# SHEET1.net
KiCad netlist of a schematic drawn in Altium Designer
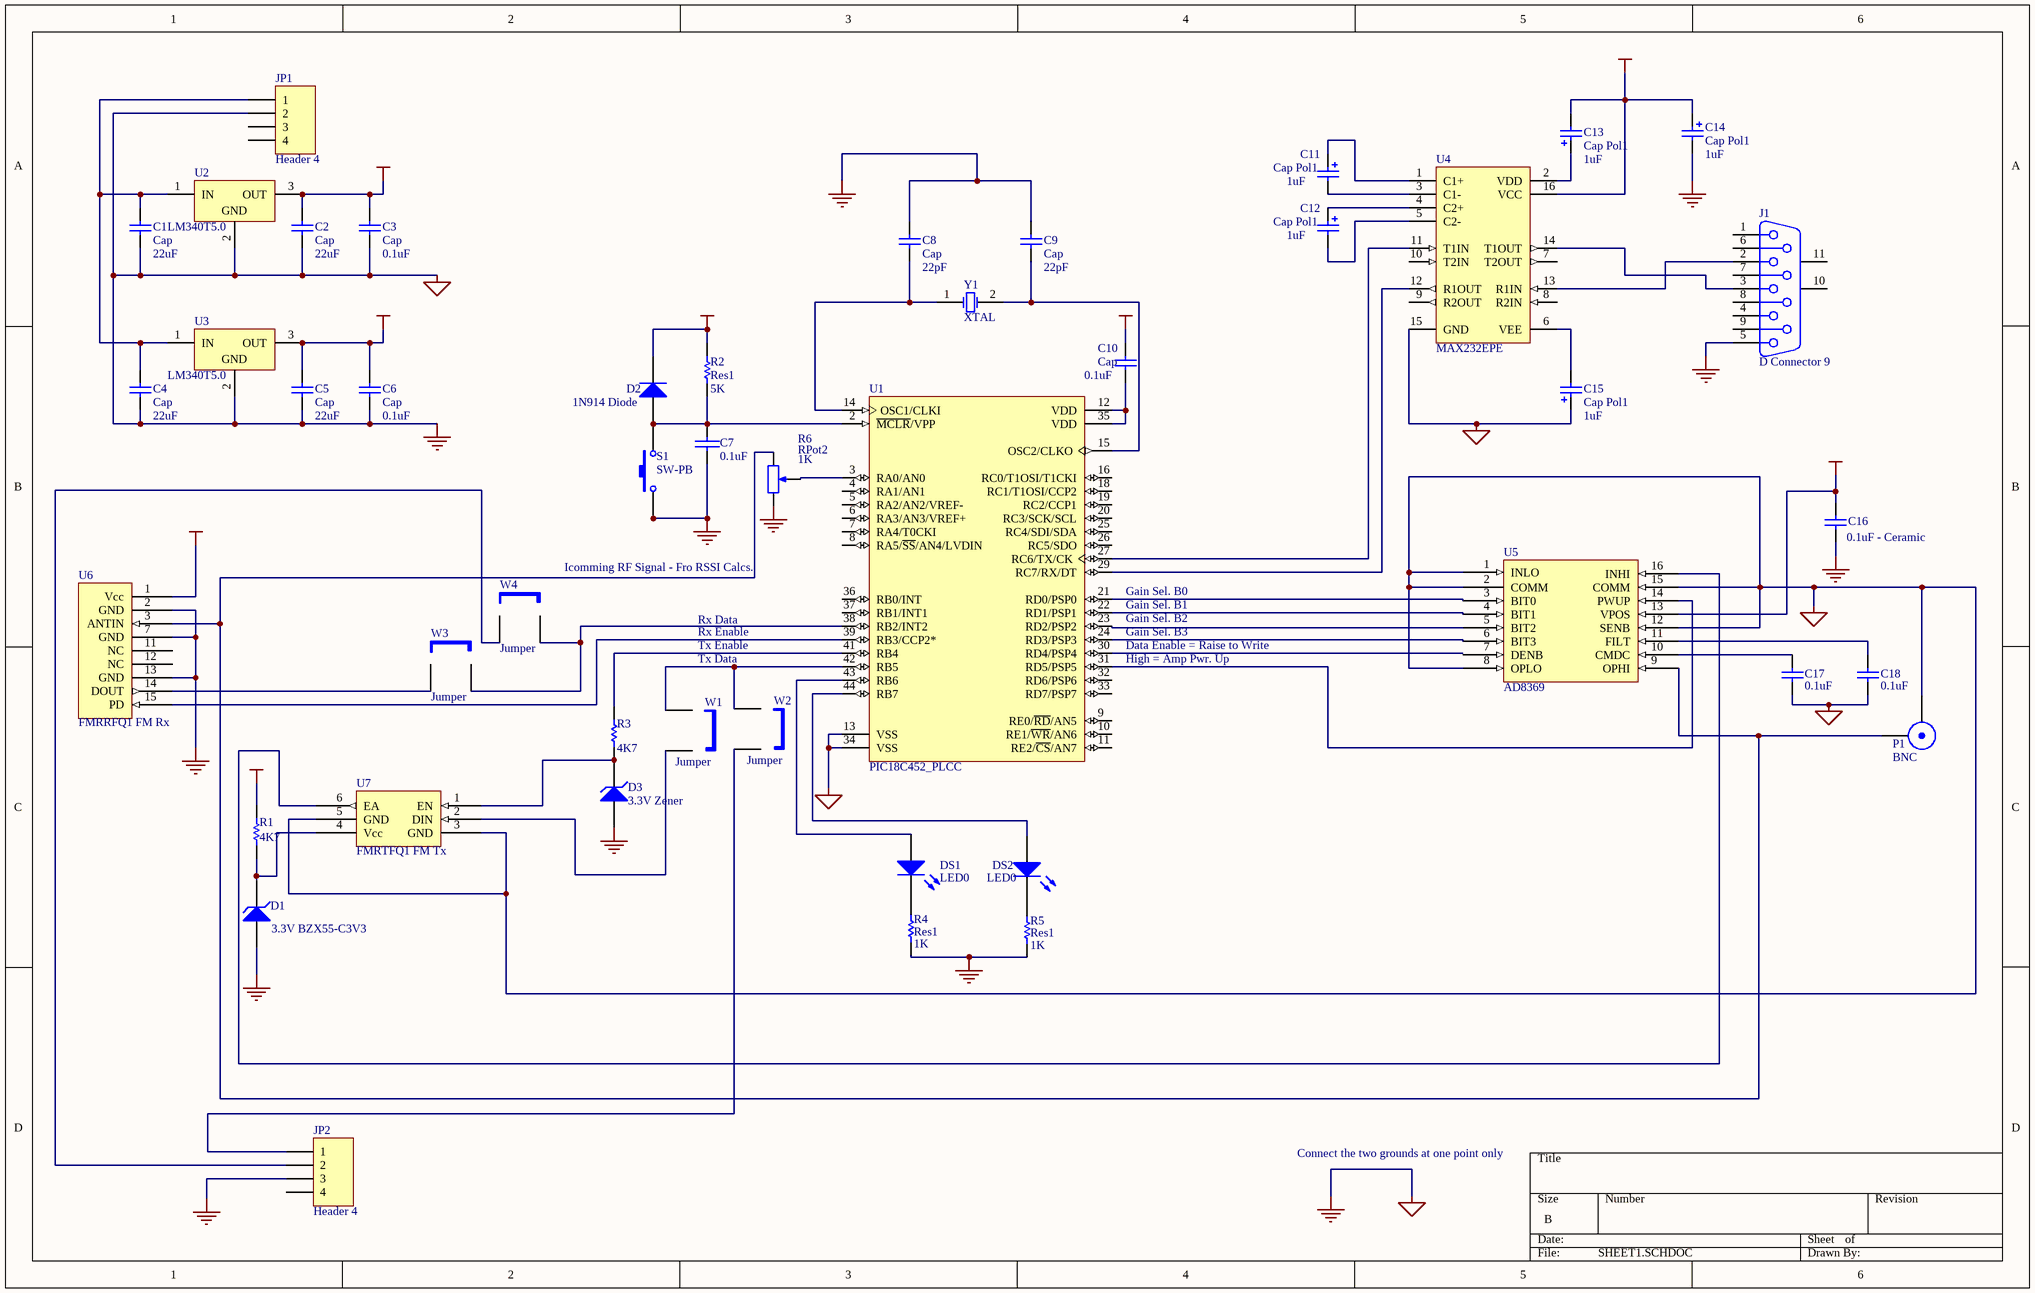
[diagram p0: SHEET1.SCHDOC]

(export (version "E")
  (design (tool "Eeschema 10.0.6"))
  (components
    (comp (ref "C1")
      (value "Cap")
      (footprint "2mm Pol. Cap")
      (description "Capacitor")
      (fields
        (field (name "MANUFACTURER") "Generic Components")
        (field (name "ALTIUM_VALUE") "22uF")
        (field (name "PUBLISHER") "Altium Limited")
      )
      (libsource (lib "Miscellaneous Devices") (part "Cap"))
    )
    (comp (ref "C2")
      (value "Cap")
      (footprint "2mm Pol. Cap")
      (description "Capacitor")
      (fields
        (field (name "MANUFACTURER") "Generic Components")
        (field (name "ALTIUM_VALUE") "22uF")
        (field (name "PUBLISHER") "Altium Limited")
      )
      (libsource (lib "Miscellaneous Devices") (part "Cap"))
    )
    (comp (ref "C3")
      (value "Cap")
      (footprint "5mm Tant. Cap")
      (description "Capacitor")
      (fields
        (field (name "MANUFACTURER") "Generic Components")
        (field (name "ALTIUM_VALUE") "0.1uF")
        (field (name "PUBLISHER") "Altium Limited")
      )
      (libsource (lib "Miscellaneous Devices") (part "Cap"))
    )
    (comp (ref "C4")
      (value "Cap")
      (footprint "2mm Pol. Cap")
      (description "Capacitor")
      (fields
        (field (name "MANUFACTURER") "Generic Components")
        (field (name "ALTIUM_VALUE") "22uF")
        (field (name "PUBLISHER") "Altium Limited")
      )
      (libsource (lib "Miscellaneous Devices") (part "Cap"))
    )
    (comp (ref "C5")
      (value "Cap")
      (footprint "2mm Pol. Cap")
      (description "Capacitor")
      (fields
        (field (name "MANUFACTURER") "Generic Components")
        (field (name "ALTIUM_VALUE") "22uF")
        (field (name "PUBLISHER") "Altium Limited")
      )
      (libsource (lib "Miscellaneous Devices") (part "Cap"))
    )
    (comp (ref "C6")
      (value "Cap")
      (footprint "5mm Tant. Cap")
      (description "Capacitor")
      (fields
        (field (name "MANUFACTURER") "Generic Components")
        (field (name "ALTIUM_VALUE") "0.1uF")
        (field (name "PUBLISHER") "Altium Limited")
      )
      (libsource (lib "Miscellaneous Devices") (part "Cap"))
    )
    (comp (ref "C7")
      (value "0.1uF")
      (footprint "5mm Tant. Cap")
      (description "Capacitor")
      (libsource (lib "*") (part "CAP"))
    )
    (comp (ref "C8")
      (value "Cap")
      (footprint "5.6mm Ceramic Cap")
      (description "Capacitor")
      (fields
        (field (name "MANUFACTURER") "Generic Components")
        (field (name "ALTIUM_VALUE") "22pF")
        (field (name "PUBLISHER") "Altium Limited")
      )
      (libsource (lib "Miscellaneous Devices") (part "Cap"))
    )
    (comp (ref "C9")
      (value "Cap")
      (footprint "5.6mm Ceramic Cap")
      (description "Capacitor")
      (fields
        (field (name "MANUFACTURER") "Generic Components")
        (field (name "ALTIUM_VALUE") "22pF")
        (field (name "PUBLISHER") "Altium Limited")
      )
      (libsource (lib "Miscellaneous Devices") (part "Cap"))
    )
    (comp (ref "C10")
      (value "Cap")
      (footprint "5mm Tant. Cap")
      (description "Capacitor")
      (fields
        (field (name "MANUFACTURER") "Generic Components")
        (field (name "ALTIUM_VALUE") "0.1uF")
        (field (name "PUBLISHER") "Altium Limited")
      )
      (libsource (lib "Miscellaneous Devices") (part "Cap"))
    )
    (comp (ref "C11")
      (value "Cap Pol1")
      (footprint "2mm Pol. Cap")
      (description "Polarized Capacitor (Radial)")
      (fields
        (field (name "MANUFACTURER") "Generic Components")
        (field (name "ALTIUM_VALUE") "1uF")
        (field (name "PUBLISHER") "Altium Limited")
      )
      (libsource (lib "Miscellaneous Devices") (part "Cap Pol1"))
    )
    (comp (ref "C12")
      (value "Cap Pol1")
      (footprint "2mm Pol. Cap")
      (description "Polarized Capacitor (Radial)")
      (fields
        (field (name "MANUFACTURER") "Generic Components")
        (field (name "ALTIUM_VALUE") "1uF")
        (field (name "PUBLISHER") "Altium Limited")
      )
      (libsource (lib "Miscellaneous Devices") (part "Cap Pol1"))
    )
    (comp (ref "C13")
      (value "Cap Pol1")
      (footprint "2mm Pol. Cap")
      (description "Polarized Capacitor (Radial)")
      (fields
        (field (name "MANUFACTURER") "Generic Components")
        (field (name "ALTIUM_VALUE") "1uF")
        (field (name "PUBLISHER") "Altium Limited")
      )
      (libsource (lib "Miscellaneous Devices") (part "Cap Pol1"))
    )
    (comp (ref "C14")
      (value "Cap Pol1")
      (footprint "2mm Pol. Cap")
      (description "Polarized Capacitor (Radial)")
      (fields
        (field (name "MANUFACTURER") "Generic Components")
        (field (name "ALTIUM_VALUE") "1uF")
        (field (name "PUBLISHER") "Altium Limited")
      )
      (libsource (lib "Miscellaneous Devices") (part "Cap Pol1"))
    )
    (comp (ref "C15")
      (value "Cap Pol1")
      (footprint "2mm Pol. Cap")
      (description "Polarized Capacitor (Radial)")
      (fields
        (field (name "MANUFACTURER") "Generic Components")
        (field (name "ALTIUM_VALUE") "1uF")
        (field (name "PUBLISHER") "Altium Limited")
      )
      (libsource (lib "Miscellaneous Devices") (part "Cap Pol1"))
    )
    (comp (ref "C16")
      (value "0.1uF - Ceramic")
      (footprint "5mm Tant. Cap")
      (description "Capacitor")
      (fields (field (name "MANUFACTURER") "Generic Components") (field (name "PUBLISHER") "Altium Limited"))
      (libsource (lib "Miscellaneous Devices") (part "Cap"))
    )
    (comp (ref "C17")
      (value "0.1uF")
      (footprint "5mm Tant. Cap")
      (description "Capacitor")
      (fields (field (name "MANUFACTURER") "Generic Components") (field (name "PUBLISHER") "Altium Limited"))
      (libsource (lib "Miscellaneous Devices") (part "Cap"))
    )
    (comp (ref "C18")
      (value "0.1uF")
      (footprint "5mm Tant. Cap")
      (description "Capacitor")
      (fields (field (name "MANUFACTURER") "Generic Components") (field (name "PUBLISHER") "Altium Limited"))
      (libsource (lib "Miscellaneous Devices") (part "Cap"))
    )
    (comp (ref "D1")
      (value "3.3V BZX55-C3V3")
      (footprint "DIO7.1-3.9X1.9")
      (description "Zener Diode")
      (fields (field (name "MANUFACTURER") "Generic Components") (field (name "PUBLISHER") "Altium Limited"))
      (libsource (lib "Miscellaneous Devices") (part "D Zener"))
    )
    (comp (ref "D2")
      (value "1N914 Diode")
      (footprint "DIO7.1-3.9X1.9")
      (description "Default Diode")
      (fields (field (name "MANUFACTURER") "Generic Components") (field (name "PUBLISHER") "Altium Limited"))
      (libsource (lib "Miscellaneous Devices") (part "Diode"))
    )
    (comp (ref "D3")
      (value "3.3V Zener")
      (footprint "DIO7.1-3.9X1.9")
      (description "Zener Diode")
      (fields (field (name "MANUFACTURER") "Generic Components") (field (name "PUBLISHER") "Altium Limited"))
      (libsource (lib "Miscellaneous Devices") (part "D Zener"))
    )
    (comp (ref "DS1")
      (value "LED0")
      (footprint "LED")
      (description "Typical INFRARED GaAs LED")
      (fields (field (name "MANUFACTURER") "Generic Components") (field (name "PUBLISHER") "Altium Limited"))
      (libsource (lib "Miscellaneous Devices") (part "LED0"))
    )
    (comp (ref "DS2")
      (value "LED0")
      (footprint "LED")
      (description "Typical INFRARED GaAs LED")
      (fields (field (name "MANUFACTURER") "Generic Components") (field (name "PUBLISHER") "Altium Limited"))
      (libsource (lib "Miscellaneous Devices") (part "LED0"))
    )
    (comp (ref "J1")
      (value "D Connector 9")
      (footprint "DSUB1.385-2H9")
      (description "Receptacle Assembly, 9 Position, Right Angle")
      (fields (field (name "MANUFACTURER") "Generic Components") (field (name "PUBLISHER") "Altium Limited"))
      (libsource (lib "Miscellaneous Connectors") (part "D Connector 9"))
    )
    (comp (ref "JP1")
      (value "Header 4")
      (footprint "4 Way Terminal Block")
      (description "Header, 4-Pin")
      (fields (field (name "MANUFACTURER") "Generic Components") (field (name "PUBLISHER") "Altium Limited"))
      (libsource (lib "Miscellaneous Connectors") (part "Header 4"))
    )
    (comp (ref "JP2")
      (value "Header 4")
      (footprint "4 Way Terminal Block")
      (description "Header, 4-Pin")
      (fields (field (name "MANUFACTURER") "Generic Components") (field (name "PUBLISHER") "Altium Limited"))
      (libsource (lib "Miscellaneous Connectors") (part "Header 4"))
    )
    (comp (ref "P1")
      (value "BNC")
      (footprint "PCB BNC Connector - duplicate")
      (description "BNC Elbow Connector")
      (fields (field (name "MANUFACTURER") "Generic Components") (field (name "PUBLISHER") "Altium Limited"))
      (libsource (lib "Miscellaneous Connectors") (part "BNC"))
    )
    (comp (ref "R1")
      (value "4K7")
      (footprint "AXIAL-0.3")
      (description "Resistor")
      (fields (field (name "MANUFACTURER") "Generic Components") (field (name "PUBLISHER") "Altium Limited"))
      (libsource (lib "Miscellaneous Devices") (part "Res1"))
    )
    (comp (ref "R2")
      (value "Res1")
      (footprint "AXIAL-0.3")
      (description "Resistor")
      (fields
        (field (name "MANUFACTURER") "Generic Components")
        (field (name "ALTIUM_VALUE") "5K")
        (field (name "PUBLISHER") "Altium Limited")
      )
      (libsource (lib "Miscellaneous Devices") (part "Res1"))
    )
    (comp (ref "R3")
      (value "Res1")
      (footprint "AXIAL-0.3")
      (description "Resistor")
      (fields
        (field (name "MANUFACTURER") "Generic Components")
        (field (name "ALTIUM_VALUE") "4K7")
        (field (name "PUBLISHER") "Altium Limited")
      )
      (libsource (lib "Miscellaneous Devices") (part "Res1"))
    )
    (comp (ref "R4")
      (value "Res1")
      (footprint "AXIAL-0.3")
      (description "Resistor")
      (fields
        (field (name "MANUFACTURER") "Generic Components")
        (field (name "ALTIUM_VALUE") "1K")
        (field (name "PUBLISHER") "Altium Limited")
      )
      (libsource (lib "Miscellaneous Devices") (part "Res1"))
    )
    (comp (ref "R5")
      (value "Res1")
      (footprint "AXIAL-0.3")
      (description "Resistor")
      (fields
        (field (name "MANUFACTURER") "Generic Components")
        (field (name "ALTIUM_VALUE") "1K")
        (field (name "PUBLISHER") "Altium Limited")
      )
      (libsource (lib "Miscellaneous Devices") (part "Res1"))
    )
    (comp (ref "R6")
      (value "RPot2")
      (footprint "VR2")
      (description "Potentiometer")
      (fields
        (field (name "MANUFACTURER") "Generic Components")
        (field (name "ALTIUM_VALUE") "1K")
        (field (name "PUBLISHER") "Altium Limited")
      )
      (libsource (lib "Miscellaneous Devices") (part "RPot2"))
    )
    (comp (ref "S1")
      (value "SW-PB")
      (footprint "Reset Switch - duplicate")
      (description "Switch")
      (fields (field (name "MANUFACTURER") "Generic Components") (field (name "PUBLISHER") "Altium Limited"))
      (libsource (lib "Miscellaneous Devices") (part "SW-PB"))
    )
    (comp (ref "U1")
      (value "PIC18C452_PLCC")
      (footprint "PLCC Socket 44 way")
      (libsource (lib "Ad_Hoc_Parts") (part "PIC18C452_PLCC"))
    )
    (comp (ref "U2")
      (value "LM340T5.0")
      (footprint "SFM-T3/A4.7V")
      (description "Series 3-Terminal Positive Regulator")
      (fields
        (field (name "MANUFACTURER") "National Semiconductor")
        (field (name "PUBLISHER") "Altium Limited")
      )
      (libsource (lib "NSC Power Mgt Voltage Regulator") (part "LM340T5.0"))
    )
    (comp (ref "U3")
      (value "LM340T5.0")
      (footprint "SFM-T3/A4.7V")
      (description "Series 3-Terminal Positive Regulator")
      (fields
        (field (name "MANUFACTURER") "National Semiconductor")
        (field (name "PUBLISHER") "Altium Limited")
      )
      (libsource (lib "NSC Power Mgt Voltage Regulator") (part "LM340T5.0"))
    )
    (comp (ref "U4")
      (value "MAX232EPE")
      (footprint "DIP-16/X1.5")
      (description "+5V Powered RS-232 Driver/Receiver")
      (fields (field (name "MANUFACTURER") "Maxim") (field (name "PUBLISHER") "Altium Limited"))
      (libsource (lib "Maxim Communication Transceiver") (part "MAX232EPE"))
    )
    (comp (ref "U5")
      (value "AD8369")
      (footprint "24 pin DIP socket for TSSOP")
      (libsource (lib "Ad_Hoc_Parts") (part "AD8369_DIGITAL_CONT_PWR_AMP"))
    )
    (comp (ref "U6")
      (value "FMRRFQ1 FM Rx")
      (footprint "FMRRFQ1")
      (libsource (lib "Ad_Hoc_Parts") (part "FMRRFQ1"))
    )
    (comp (ref "U7")
      (value "FMRTFQ1 FM Tx")
      (footprint "FMRTFQ1")
      (libsource (lib "Ad_Hoc_Parts") (part "FMRTFQ1"))
    )
    (comp (ref "W1")
      (value "Jumper")
      (footprint "RAD-0.1")
      (description "Jumper Wire")
      (fields (field (name "MANUFACTURER") "Generic Components") (field (name "PUBLISHER") "Altium Limited"))
      (libsource (lib "Miscellaneous Devices") (part "Jumper"))
    )
    (comp (ref "W2")
      (value "Jumper")
      (footprint "RAD-0.1")
      (description "Jumper Wire")
      (fields (field (name "MANUFACTURER") "Generic Components") (field (name "PUBLISHER") "Altium Limited"))
      (libsource (lib "Miscellaneous Devices") (part "Jumper"))
    )
    (comp (ref "W3")
      (value "Jumper")
      (footprint "RAD-0.1")
      (description "Jumper Wire")
      (fields (field (name "MANUFACTURER") "Generic Components") (field (name "PUBLISHER") "Altium Limited"))
      (libsource (lib "Miscellaneous Devices") (part "Jumper"))
    )
    (comp (ref "W4")
      (value "Jumper")
      (footprint "RAD-0.1")
      (description "Jumper Wire")
      (fields (field (name "MANUFACTURER") "Generic Components") (field (name "PUBLISHER") "Altium Limited"))
      (libsource (lib "Miscellaneous Devices") (part "Jumper"))
    )
    (comp (ref "Y1")
      (value "XTAL")
      (footprint "XTAL")
      (description "Crystal Oscillator")
      (fields (field (name "MANUFACTURER") "Generic Components") (field (name "PUBLISHER") "Altium Limited"))
      (libsource (lib "Miscellaneous Devices") (part "XTAL"))
    )
  )
  (nets
    (net (code "1") (name "GND") (class "Default")
      (node (ref "C1") (pin "2") (pinfunction "2_2") (pintype "passive"))
      (node (ref "C14") (pin "2") (pinfunction "2_2") (pintype "passive"))
      (node (ref "C15") (pin "1") (pinfunction "1_1") (pintype "passive"))
      (node (ref "C16") (pin "2") (pinfunction "2_2") (pintype "passive"))
      (node (ref "C17") (pin "2") (pinfunction "2_2") (pintype "passive"))
      (node (ref "C18") (pin "2") (pinfunction "2_2") (pintype "passive"))
      (node (ref "C2") (pin "2") (pinfunction "2_2") (pintype "passive"))
      (node (ref "C3") (pin "2") (pinfunction "2_2") (pintype "passive"))
      (node (ref "C4") (pin "2") (pinfunction "2_2") (pintype "passive"))
      (node (ref "C5") (pin "2") (pinfunction "2_2") (pintype "passive"))
      (node (ref "C6") (pin "2") (pinfunction "2_2") (pintype "passive"))
      (node (ref "C7") (pin "2") (pinfunction "2_2") (pintype "passive"))
      (node (ref "C8") (pin "2") (pinfunction "2_2") (pintype "passive"))
      (node (ref "C9") (pin "2") (pinfunction "2_2") (pintype "passive"))
      (node (ref "D1") (pin "1") (pinfunction "A_1") (pintype "passive"))
      (node (ref "D3") (pin "1") (pinfunction "A_1") (pintype "passive"))
      (node (ref "J1") (pin "5") (pinfunction "5_5") (pintype "passive"))
      (node (ref "JP1") (pin "2") (pinfunction "2_2") (pintype "passive"))
      (node (ref "JP2") (pin "3") (pinfunction "3_3") (pintype "passive"))
      (node (ref "P1") (pin "2") (pinfunction "Y_2") (pintype "passive"))
      (node (ref "R4") (pin "2") (pinfunction "2_2") (pintype "passive"))
      (node (ref "R5") (pin "2") (pinfunction "2_2") (pintype "passive"))
      (node (ref "R6") (pin "1") (pinfunction "TOP_1") (pintype "passive"))
      (node (ref "S1") (pin "1") (pinfunction "1_1") (pintype "passive"))
      (node (ref "U1") (pin "13") (pinfunction "VSS_13") (pintype "power_in"))
      (node (ref "U1") (pin "34") (pinfunction "VSS_34") (pintype "power_in"))
      (node (ref "U2") (pin "2") (pinfunction "GND_2") (pintype "power_in"))
      (node (ref "U3") (pin "2") (pinfunction "GND_2") (pintype "power_in"))
      (node (ref "U4") (pin "15") (pinfunction "GND_15") (pintype "power_in"))
      (node (ref "U5") (pin "12") (pinfunction "SENB_12") (pintype "input"))
      (node (ref "U5") (pin "15") (pinfunction "COMM_15") (pintype "input"))
      (node (ref "U6") (pin "13") (pinfunction "GND_13") (pintype "passive"))
      (node (ref "U6") (pin "2") (pinfunction "GND_2") (pintype "passive"))
      (node (ref "U6") (pin "7") (pinfunction "GND_7") (pintype "passive"))
      (node (ref "U7") (pin "3") (pinfunction "GND_3") (pintype "passive"))
      (node (ref "U7") (pin "5") (pinfunction "GND_5") (pintype "passive"))
    )
    (net (code "2") (name "Net-(C10-Pad2)") (class "Default")
      (node (ref "C10") (pin "2") (pinfunction "2_2") (pintype "passive"))
      (node (ref "U1") (pin "12") (pinfunction "VDD_12") (pintype "power_in"))
      (node (ref "U1") (pin "35") (pinfunction "VDD_35") (pintype "power_in"))
    )
    (net (code "3") (name "Net-(D1-K)") (class "Default")
      (node (ref "D1") (pin "2") (pinfunction "K_2") (pintype "passive"))
      (node (ref "R1") (pin "1") (pinfunction "1_1") (pintype "passive"))
      (node (ref "U7") (pin "4") (pinfunction "Vcc_4") (pintype "passive"))
    )
    (net (code "4") (name "Net-(D2-A)") (class "Default")
      (node (ref "C7") (pin "1") (pinfunction "1_1") (pintype "passive"))
      (node (ref "D2") (pin "1") (pinfunction "A_1") (pintype "passive"))
      (node (ref "R2") (pin "1") (pinfunction "1_1") (pintype "passive"))
      (node (ref "S1") (pin "2") (pinfunction "2_2") (pintype "passive"))
      (node (ref "U1") (pin "2") (pinfunction "~{MCLR}/VPP_2") (pintype "input"))
    )
    (net (code "5") (name "Net-(D3-K)") (class "Default")
      (node (ref "D3") (pin "2") (pinfunction "K_2") (pintype "passive"))
      (node (ref "R3") (pin "1") (pinfunction "1_1") (pintype "passive"))
      (node (ref "U7") (pin "1") (pinfunction "EN_1") (pintype "input"))
    )
    (net (code "6") (name "Net-(DS1-A)") (class "Default")
      (node (ref "DS1") (pin "1") (pinfunction "A_1") (pintype "passive"))
      (node (ref "U1") (pin "43") (pinfunction "RB6_43") (pintype "bidirectional"))
    )
    (net (code "7") (name "Net-(DS1-K)") (class "Default")
      (node (ref "DS1") (pin "2") (pinfunction "K_2") (pintype "passive"))
      (node (ref "R4") (pin "1") (pinfunction "1_1") (pintype "passive"))
    )
    (net (code "8") (name "Net-(DS2-A)") (class "Default")
      (node (ref "DS2") (pin "1") (pinfunction "A_1") (pintype "passive"))
      (node (ref "U1") (pin "44") (pinfunction "RB7_44") (pintype "bidirectional"))
    )
    (net (code "9") (name "Net-(DS2-K)") (class "Default")
      (node (ref "DS2") (pin "2") (pinfunction "K_2") (pintype "passive"))
      (node (ref "R5") (pin "1") (pinfunction "1_1") (pintype "passive"))
    )
    (net (code "10") (name "Net-(JP2-Pad1)") (class "Default")
      (node (ref "JP2") (pin "1") (pinfunction "1_1") (pintype "passive"))
      (node (ref "W2") (pin "2") (pinfunction "2_2") (pintype "passive"))
    )
    (net (code "11") (name "Net-(JP2-Pad2)") (class "Default")
      (node (ref "JP2") (pin "2") (pinfunction "2_2") (pintype "passive"))
      (node (ref "W4") (pin "1") (pinfunction "1_1") (pintype "passive"))
    )
    (net (code "12") (name "Net-(P1-X)") (class "Default")
      (node (ref "P1") (pin "1") (pinfunction "X_1") (pintype "passive"))
      (node (ref "R6") (pin "2") (pinfunction "BOT_2") (pintype "passive"))
      (node (ref "U5") (pin "9") (pinfunction "OPHI_9") (pintype "input"))
      (node (ref "U6") (pin "3") (pinfunction "ANTIN_3") (pintype "input"))
    )
    (net (code "13") (name "Net-(R6-TAP)") (class "Default")
      (node (ref "R6") (pin "3") (pinfunction "TAP_3") (pintype "passive"))
      (node (ref "U1") (pin "3") (pinfunction "RA0/AN0_3") (pintype "bidirectional"))
    )
    (net (code "14") (name "Net-(U1-OSC1{slash}CLKI)") (class "Default")
      (node (ref "C8") (pin "1") (pinfunction "1_1") (pintype "passive"))
      (node (ref "U1") (pin "14") (pinfunction "OSC1/CLKI_14") (pintype "input"))
      (node (ref "Y1") (pin "1") (pinfunction "OSC1_1") (pintype "passive"))
    )
    (net (code "15") (name "Net-(U1-OSC2{slash}CLKO)") (class "Default")
      (node (ref "C9") (pin "1") (pinfunction "1_1") (pintype "passive"))
      (node (ref "U1") (pin "15") (pinfunction "OSC2/CLKO_15") (pintype "output"))
      (node (ref "Y1") (pin "2") (pinfunction "OSC2_2") (pintype "passive"))
    )
    (net (code "16") (name "Net-(U1-RB2{slash}INT2)") (class "Default")
      (node (ref "U1") (pin "38") (pinfunction "RB2/INT2_38") (pintype "bidirectional"))
      (node (ref "W3") (pin "2") (pinfunction "2_2") (pintype "passive"))
      (node (ref "W4") (pin "2") (pinfunction "2_2") (pintype "passive"))
    )
    (net (code "17") (name "Net-(U1-RB3{slash}CCP2*)") (class "Default")
      (node (ref "U1") (pin "39") (pinfunction "RB3/CCP2*_39") (pintype "bidirectional"))
      (node (ref "U6") (pin "15") (pinfunction "PD_15") (pintype "input"))
    )
    (net (code "18") (name "Net-(U1-RB4)") (class "Default")
      (node (ref "R3") (pin "2") (pinfunction "2_2") (pintype "passive"))
      (node (ref "U1") (pin "41") (pinfunction "RB4_41") (pintype "bidirectional"))
    )
    (net (code "19") (name "Net-(U1-RB5)") (class "Default")
      (node (ref "U1") (pin "42") (pinfunction "RB5_42") (pintype "bidirectional"))
      (node (ref "W1") (pin "1") (pinfunction "1_1") (pintype "passive"))
      (node (ref "W2") (pin "1") (pinfunction "1_1") (pintype "passive"))
    )
    (net (code "20") (name "Net-(U1-RC6{slash}TX{slash}CK)") (class "Default")
      (node (ref "U1") (pin "27") (pinfunction "RC6/TX/CK_27") (pintype "bidirectional"))
      (node (ref "U4") (pin "11") (pinfunction "T1IN_11") (pintype "input"))
    )
    (net (code "21") (name "Net-(U1-RC7{slash}RX{slash}DT)") (class "Default")
      (node (ref "U1") (pin "29") (pinfunction "RC7/RX/DT_29") (pintype "bidirectional"))
      (node (ref "U4") (pin "12") (pinfunction "R1OUT_12") (pintype "output"))
    )
    (net (code "22") (name "Net-(U1-RD0{slash}PSP0)") (class "Default")
      (node (ref "U1") (pin "21") (pinfunction "RD0/PSP0_21") (pintype "bidirectional"))
      (node (ref "U5") (pin "3") (pinfunction "BIT0_3") (pintype "input"))
    )
    (net (code "23") (name "Net-(U1-RD1{slash}PSP1)") (class "Default")
      (node (ref "U1") (pin "22") (pinfunction "RD1/PSP1_22") (pintype "bidirectional"))
      (node (ref "U5") (pin "4") (pinfunction "BIT1_4") (pintype "input"))
    )
    (net (code "24") (name "Net-(U1-RD2{slash}PSP2)") (class "Default")
      (node (ref "U1") (pin "23") (pinfunction "RD2/PSP2_23") (pintype "bidirectional"))
      (node (ref "U5") (pin "5") (pinfunction "BIT2_5") (pintype "input"))
    )
    (net (code "25") (name "Net-(U1-RD3{slash}PSP3)") (class "Default")
      (node (ref "U1") (pin "24") (pinfunction "RD3/PSP3_24") (pintype "bidirectional"))
      (node (ref "U5") (pin "6") (pinfunction "BIT3_6") (pintype "input"))
    )
    (net (code "26") (name "Net-(U1-RD5{slash}PSP5)") (class "Default")
      (node (ref "U1") (pin "31") (pinfunction "RD5/PSP5_31") (pintype "bidirectional"))
      (node (ref "U5") (pin "14") (pinfunction "PWUP_14") (pintype "input"))
    )
    (net (code "27") (name "Net-(U2-IN)") (class "Default")
      (node (ref "C1") (pin "1") (pinfunction "1_1") (pintype "passive"))
      (node (ref "C4") (pin "1") (pinfunction "1_1") (pintype "passive"))
      (node (ref "JP1") (pin "1") (pinfunction "1_1") (pintype "passive"))
      (node (ref "U2") (pin "1") (pinfunction "IN_1") (pintype "power_in"))
      (node (ref "U3") (pin "1") (pinfunction "IN_1") (pintype "power_in"))
    )
    (net (code "28") (name "Net-(U4-C1+)") (class "Default")
      (node (ref "C11") (pin "1") (pinfunction "1_1") (pintype "passive"))
      (node (ref "U4") (pin "1") (pinfunction "C1+_1") (pintype "passive"))
    )
    (net (code "29") (name "Net-(U4-C1-)") (class "Default")
      (node (ref "C11") (pin "2") (pinfunction "2_2") (pintype "passive"))
      (node (ref "U4") (pin "3") (pinfunction "C1-_3") (pintype "passive"))
    )
    (net (code "30") (name "Net-(U4-C2+)") (class "Default")
      (node (ref "C12") (pin "1") (pinfunction "1_1") (pintype "passive"))
      (node (ref "U4") (pin "4") (pinfunction "C2+_4") (pintype "passive"))
    )
    (net (code "31") (name "Net-(U4-C2-)") (class "Default")
      (node (ref "C12") (pin "2") (pinfunction "2_2") (pintype "passive"))
      (node (ref "U4") (pin "5") (pinfunction "C2-_5") (pintype "passive"))
    )
    (net (code "32") (name "Net-(U4-R1IN)") (class "Default")
      (node (ref "J1") (pin "2") (pinfunction "2_2") (pintype "passive"))
      (node (ref "U4") (pin "13") (pinfunction "R1IN_13") (pintype "input"))
    )
    (net (code "33") (name "Net-(U4-T1OUT)") (class "Default")
      (node (ref "J1") (pin "3") (pinfunction "3_3") (pintype "passive"))
      (node (ref "U4") (pin "14") (pinfunction "T1OUT_14") (pintype "output"))
    )
    (net (code "34") (name "Net-(U4-VDD)") (class "Default")
      (node (ref "C13") (pin "1") (pinfunction "1_1") (pintype "passive"))
      (node (ref "U4") (pin "2") (pinfunction "VDD_2") (pintype "power_in"))
    )
    (net (code "35") (name "Net-(U4-VEE)") (class "Default")
      (node (ref "C15") (pin "2") (pinfunction "2_2") (pintype "passive"))
      (node (ref "U4") (pin "6") (pinfunction "VEE_6") (pintype "power_in"))
    )
    (net (code "36") (name "Net-(U5-CMDC)") (class "Default")
      (node (ref "C17") (pin "1") (pinfunction "1_1") (pintype "passive"))
      (node (ref "U5") (pin "10") (pinfunction "CMDC_10") (pintype "input"))
    )
    (net (code "37") (name "Net-(U5-FILT)") (class "Default")
      (node (ref "C18") (pin "1") (pinfunction "1_1") (pintype "passive"))
      (node (ref "U5") (pin "11") (pinfunction "FILT_11") (pintype "input"))
    )
    (net (code "38") (name "Net-(U5-INHI)") (class "Default")
      (node (ref "U5") (pin "16") (pinfunction "INHI_16") (pintype "input"))
      (node (ref "U7") (pin "6") (pinfunction "EA_6") (pintype "output"))
    )
    (net (code "39") (name "Net-(U5-INLO)") (class "Default")
      (node (ref "U5") (pin "1") (pinfunction "INLO_1") (pintype "input"))
      (node (ref "U5") (pin "2") (pinfunction "COMM_2") (pintype "power_in"))
      (node (ref "U5") (pin "8") (pinfunction "OPLO_8") (pintype "input"))
    )
    (net (code "40") (name "Net-(U6-DOUT)") (class "Default")
      (node (ref "U6") (pin "14") (pinfunction "DOUT_14") (pintype "output"))
      (node (ref "W3") (pin "1") (pinfunction "1_1") (pintype "passive"))
    )
    (net (code "41") (name "Net-(U7-DIN)") (class "Default")
      (node (ref "U7") (pin "2") (pinfunction "DIN_2") (pintype "input"))
      (node (ref "W1") (pin "2") (pinfunction "2_2") (pintype "passive"))
    )
    (net (code "42") (name "VCC") (class "Default")
      (node (ref "C13") (pin "2") (pinfunction "2_2") (pintype "passive"))
      (node (ref "C14") (pin "1") (pinfunction "1_1") (pintype "passive"))
      (node (ref "C16") (pin "1") (pinfunction "1_1") (pintype "passive"))
      (node (ref "C2") (pin "1") (pinfunction "1_1") (pintype "passive"))
      (node (ref "C3") (pin "1") (pinfunction "1_1") (pintype "passive"))
      (node (ref "D2") (pin "2") (pinfunction "K_2") (pintype "passive"))
      (node (ref "R1") (pin "2") (pinfunction "2_2") (pintype "passive"))
      (node (ref "R2") (pin "2") (pinfunction "2_2") (pintype "passive"))
      (node (ref "U2") (pin "3") (pinfunction "OUT_3") (pintype "power_in"))
      (node (ref "U4") (pin "16") (pinfunction "VCC_16") (pintype "power_in"))
      (node (ref "U5") (pin "13") (pinfunction "VPOS_13") (pintype "input"))
      (node (ref "U6") (pin "1") (pinfunction "Vcc_1") (pintype "passive"))
    )
    (net (code "43") (name "VDD") (class "Default")
      (node (ref "C10") (pin "1") (pinfunction "1_1") (pintype "passive"))
      (node (ref "C5") (pin "1") (pinfunction "1_1") (pintype "passive"))
      (node (ref "C6") (pin "1") (pinfunction "1_1") (pintype "passive"))
      (node (ref "U3") (pin "3") (pinfunction "OUT_3") (pintype "power_in"))
    )
    (net (code "44") (name "unconnected-(J1-MH1-Pad10)") (class "Default")
      (node (ref "J1") (pin "10") (pinfunction "MH1_10") (pintype "passive"))
    )
    (net (code "45") (name "unconnected-(J1-MH2-Pad11)") (class "Default")
      (node (ref "J1") (pin "11") (pinfunction "MH2_11") (pintype "passive"))
    )
    (net (code "46") (name "unconnected-(J1-Pad1)") (class "Default")
      (node (ref "J1") (pin "1") (pinfunction "1_1") (pintype "passive"))
    )
    (net (code "47") (name "unconnected-(J1-Pad4)") (class "Default")
      (node (ref "J1") (pin "4") (pinfunction "4_4") (pintype "passive"))
    )
    (net (code "48") (name "unconnected-(J1-Pad6)") (class "Default")
      (node (ref "J1") (pin "6") (pinfunction "6_6") (pintype "passive"))
    )
    (net (code "49") (name "unconnected-(J1-Pad7)") (class "Default")
      (node (ref "J1") (pin "7") (pinfunction "7_7") (pintype "passive"))
    )
    (net (code "50") (name "unconnected-(J1-Pad8)") (class "Default")
      (node (ref "J1") (pin "8") (pinfunction "8_8") (pintype "passive"))
    )
    (net (code "51") (name "unconnected-(J1-Pad9)") (class "Default")
      (node (ref "J1") (pin "9") (pinfunction "9_9") (pintype "passive"))
    )
    (net (code "52") (name "unconnected-(JP1-Pad3)") (class "Default")
      (node (ref "JP1") (pin "3") (pinfunction "3_3") (pintype "passive"))
    )
    (net (code "53") (name "unconnected-(JP1-Pad4)") (class "Default")
      (node (ref "JP1") (pin "4") (pinfunction "4_4") (pintype "passive"))
    )
    (net (code "54") (name "unconnected-(JP2-Pad4)") (class "Default")
      (node (ref "JP2") (pin "4") (pinfunction "4_4") (pintype "passive"))
    )
    (net (code "55") (name "unconnected-(U1-RA1{slash}AN1-Pad4)") (class "Default")
      (node (ref "U1") (pin "4") (pinfunction "RA1/AN1_4") (pintype "bidirectional"))
    )
    (net (code "56") (name "unconnected-(U1-RA2{slash}AN2{slash}VREF--Pad5)") (class "Default")
      (node (ref "U1") (pin "5") (pinfunction "RA2/AN2/VREF-_5") (pintype "bidirectional"))
    )
    (net (code "57") (name "unconnected-(U1-RA3{slash}AN3{slash}VREF+-Pad6)") (class "Default")
      (node (ref "U1") (pin "6") (pinfunction "RA3/AN3/VREF+_6") (pintype "bidirectional"))
    )
    (net (code "58") (name "unconnected-(U1-RA4{slash}T0CKI-Pad7)") (class "Default")
      (node (ref "U1") (pin "7") (pinfunction "RA4/T0CKI_7") (pintype "bidirectional"))
    )
    (net (code "59") (name "unconnected-(U1-RA5{slash}~{SS}{slash}AN4{slash}LVDIN-Pad8)") (class "Default")
      (node (ref "U1") (pin "8") (pinfunction "RA5/~{SS}/AN4/LVDIN_8") (pintype "bidirectional"))
    )
    (net (code "60") (name "unconnected-(U1-RB0{slash}INT-Pad36)") (class "Default")
      (node (ref "U1") (pin "36") (pinfunction "RB0/INT_36") (pintype "bidirectional"))
    )
    (net (code "61") (name "unconnected-(U1-RB1{slash}INT1-Pad37)") (class "Default")
      (node (ref "U1") (pin "37") (pinfunction "RB1/INT1_37") (pintype "bidirectional"))
    )
    (net (code "62") (name "unconnected-(U1-RC0{slash}T1OSI{slash}T1CKI-Pad16)") (class "Default")
      (node (ref "U1") (pin "16") (pinfunction "RC0/T1OSI/T1CKI_16") (pintype "bidirectional"))
    )
    (net (code "63") (name "unconnected-(U1-RC1{slash}T1OSI{slash}CCP2-Pad18)") (class "Default")
      (node (ref "U1") (pin "18") (pinfunction "RC1/T1OSI/CCP2_18") (pintype "bidirectional"))
    )
    (net (code "64") (name "unconnected-(U1-RC2{slash}CCP1-Pad19)") (class "Default")
      (node (ref "U1") (pin "19") (pinfunction "RC2/CCP1_19") (pintype "bidirectional"))
    )
    (net (code "65") (name "unconnected-(U1-RC3{slash}SCK{slash}SCL-Pad20)") (class "Default")
      (node (ref "U1") (pin "20") (pinfunction "RC3/SCK/SCL_20") (pintype "bidirectional"))
    )
    (net (code "66") (name "unconnected-(U1-RC4{slash}SDI{slash}SDA-Pad25)") (class "Default")
      (node (ref "U1") (pin "25") (pinfunction "RC4/SDI/SDA_25") (pintype "bidirectional"))
    )
    (net (code "67") (name "unconnected-(U1-RC5{slash}SDO-Pad26)") (class "Default")
      (node (ref "U1") (pin "26") (pinfunction "RC5/SDO_26") (pintype "bidirectional"))
    )
    (net (code "68") (name "unconnected-(U1-RD4{slash}PSP4-Pad30)") (class "Default")
      (node (ref "U1") (pin "30") (pinfunction "RD4/PSP4_30") (pintype "bidirectional"))
    )
    (net (code "69") (name "unconnected-(U1-RD6{slash}PSP6-Pad32)") (class "Default")
      (node (ref "U1") (pin "32") (pinfunction "RD6/PSP6_32") (pintype "bidirectional"))
    )
    (net (code "70") (name "unconnected-(U1-RD7{slash}PSP7-Pad33)") (class "Default")
      (node (ref "U1") (pin "33") (pinfunction "RD7/PSP7_33") (pintype "bidirectional"))
    )
    (net (code "71") (name "unconnected-(U1-RE0{slash}~{RD}{slash}AN5-Pad9)") (class "Default")
      (node (ref "U1") (pin "9") (pinfunction "RE0/~{RD}/AN5_9") (pintype "bidirectional"))
    )
    (net (code "72") (name "unconnected-(U1-RE1{slash}~{WR}{slash}AN6-Pad10)") (class "Default")
      (node (ref "U1") (pin "10") (pinfunction "RE1/~{WR}/AN6_10") (pintype "bidirectional"))
    )
    (net (code "73") (name "unconnected-(U1-RE2{slash}~{CS}{slash}AN7-Pad11)") (class "Default")
      (node (ref "U1") (pin "11") (pinfunction "RE2/~{CS}/AN7_11") (pintype "bidirectional"))
    )
    (net (code "74") (name "unconnected-(U4-R2IN-Pad8)") (class "Default")
      (node (ref "U4") (pin "8") (pinfunction "R2IN_8") (pintype "input"))
    )
    (net (code "75") (name "unconnected-(U4-R2OUT-Pad9)") (class "Default")
      (node (ref "U4") (pin "9") (pinfunction "R2OUT_9") (pintype "output"))
    )
    (net (code "76") (name "unconnected-(U4-T2IN-Pad10)") (class "Default")
      (node (ref "U4") (pin "10") (pinfunction "T2IN_10") (pintype "input"))
    )
    (net (code "77") (name "unconnected-(U4-T2OUT-Pad7)") (class "Default")
      (node (ref "U4") (pin "7") (pinfunction "T2OUT_7") (pintype "output"))
    )
    (net (code "78") (name "unconnected-(U5-DENB-Pad7)") (class "Default")
      (node (ref "U5") (pin "7") (pinfunction "DENB_7") (pintype "input"))
    )
    (net (code "79") (name "unconnected-(U6-NC-Pad11)") (class "Default")
      (node (ref "U6") (pin "11") (pinfunction "NC_11") (pintype "passive"))
    )
    (net (code "80") (name "unconnected-(U6-NC-Pad12)") (class "Default")
      (node (ref "U6") (pin "12") (pinfunction "NC_12") (pintype "passive"))
    )
  )
)
